# Main.net
KiCad netlist of a schematic drawn in EAGLE
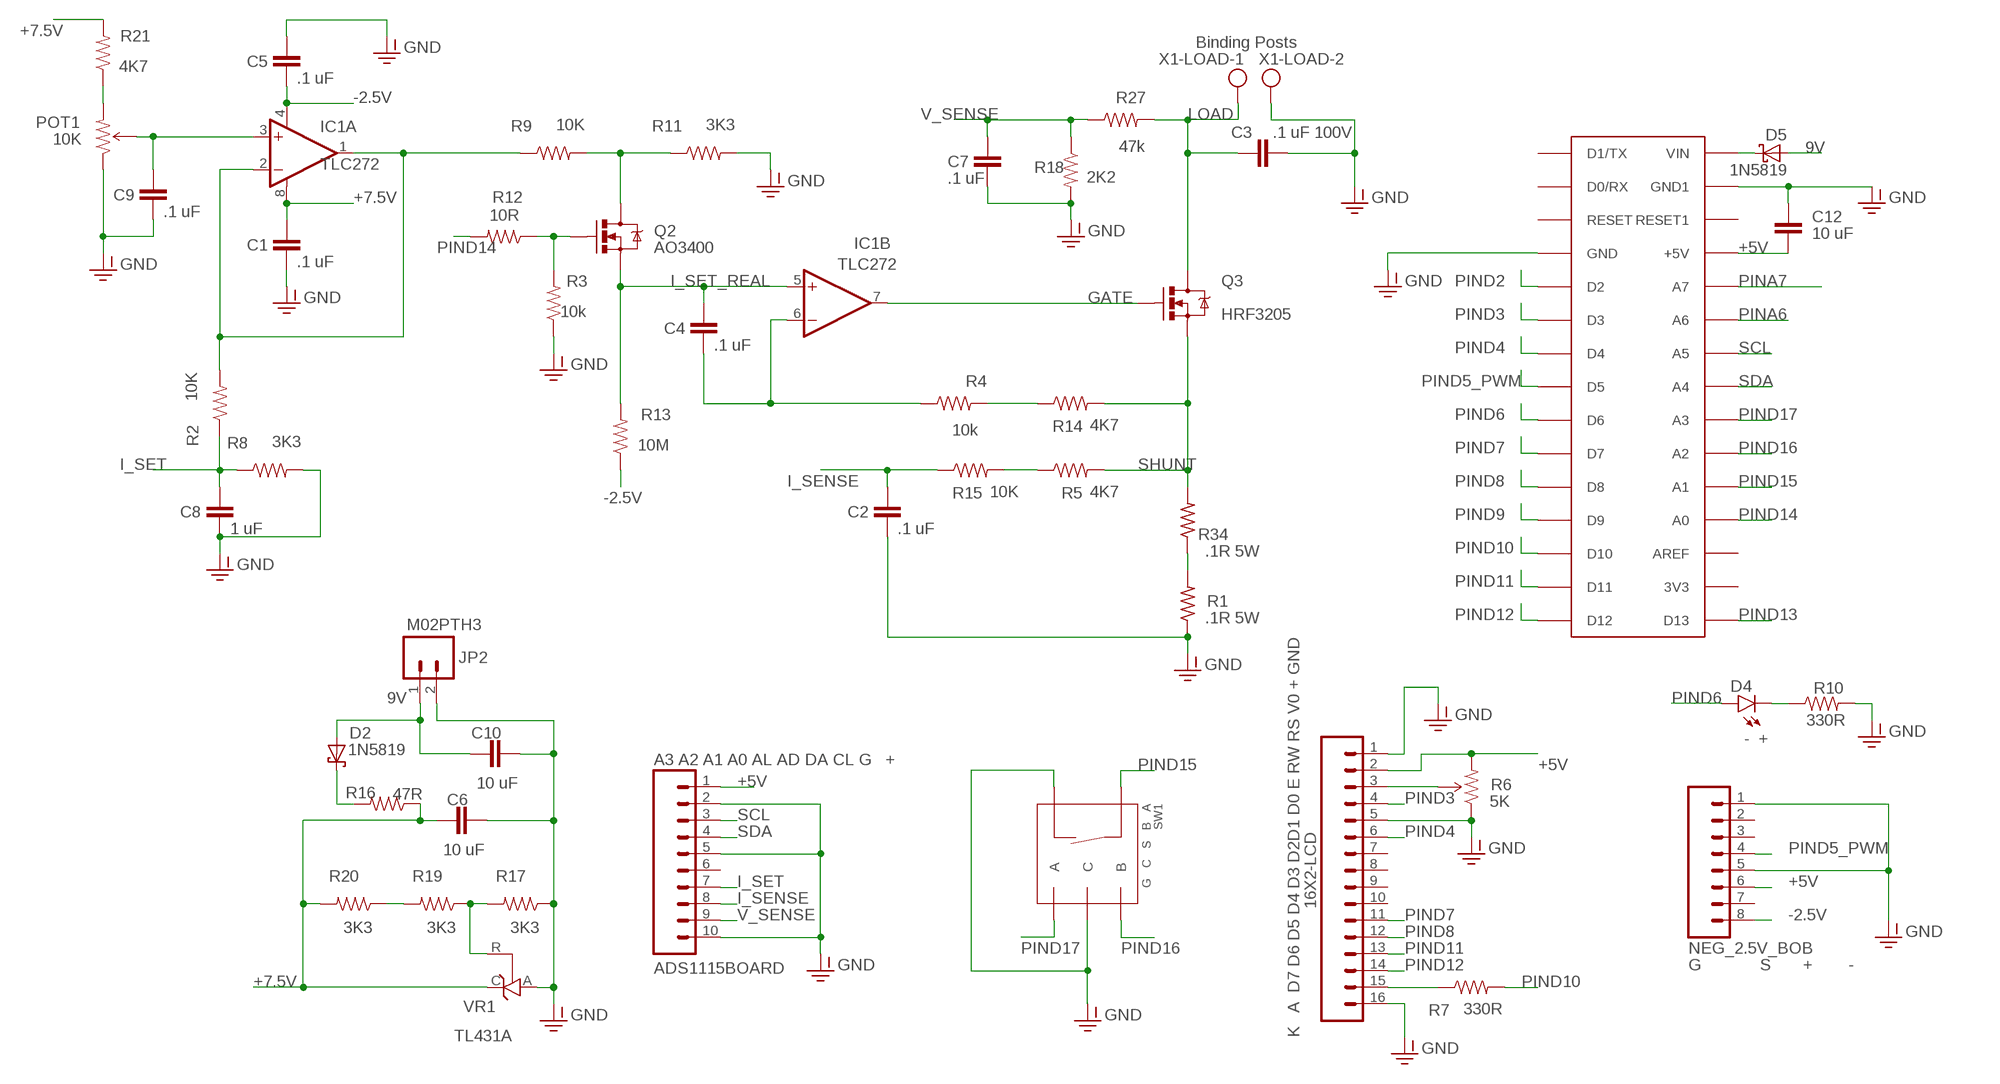
[diagram p0: schematic, sheet 1]
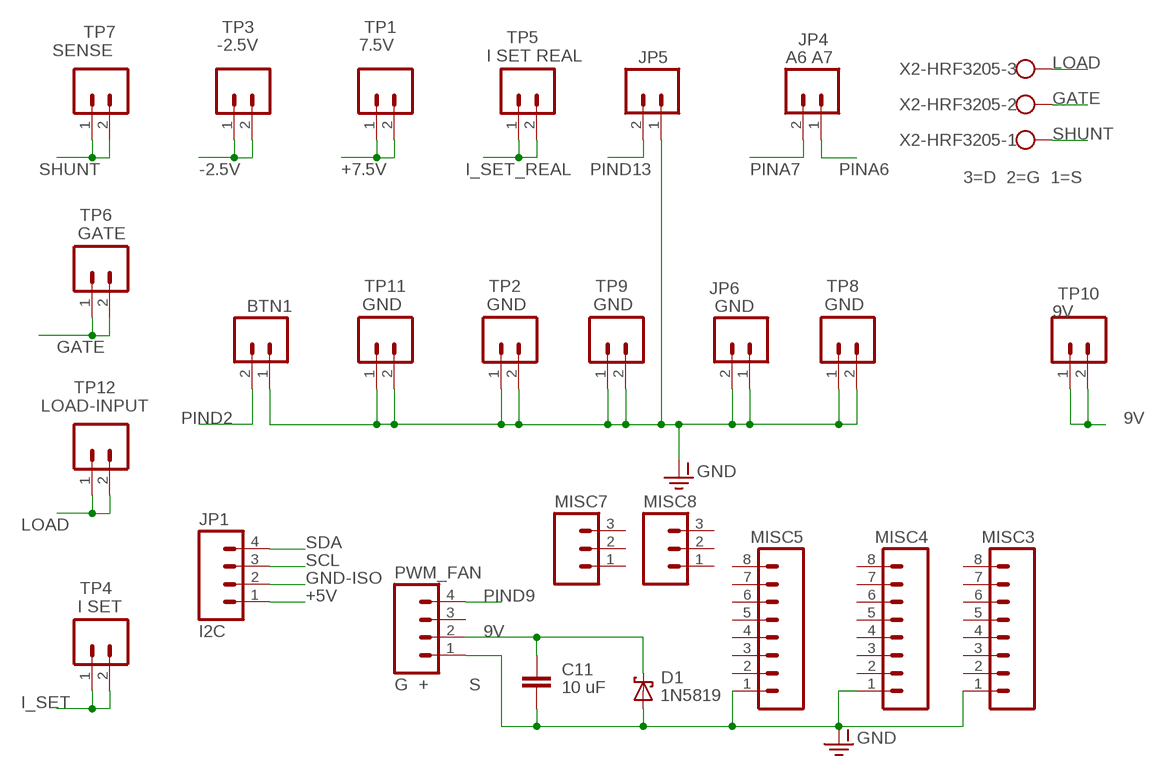
[diagram p1: schematic, sheet 2]

(export (version "E")
  (design (tool "Eeschema 10.0.6"))
  (components
    (comp (ref "BTN1")
      (value "M02PTH")
      (footprint "eagle-import:1X02")
      (libsource (lib "eagle-import") (part "M02PTH"))
    )
    (comp (ref "C11")
      (value "10 uF")
      (footprint "eagle-import:CAP-PTH-5MM")
      (libsource (lib "eagle-import") (part "CAPPTH1"))
    )
    (comp (ref "D1")
      (value "1N5819")
      (footprint "eagle-import:DO41-10")
      (libsource (lib "eagle-import") (part "1N5819"))
    )
    (comp (ref "JP1")
      (value "I2C")
      (footprint "eagle-import:1X04")
      (libsource (lib "eagle-import") (part "M04PTH"))
    )
    (comp (ref "JP4")
      (value "A6 A7")
      (footprint "eagle-import:1X02")
      (libsource (lib "eagle-import") (part "M02PTH"))
    )
    (comp (ref "JP5")
      (value "M02PTH")
      (footprint "eagle-import:1X02")
      (libsource (lib "eagle-import") (part "M02PTH"))
    )
    (comp (ref "JP6")
      (value "GND")
      (footprint "eagle-import:1X02")
      (libsource (lib "eagle-import") (part "M02PTH"))
    )
    (comp (ref "MISC3")
      (value "M08")
      (footprint "eagle-import:1X08_ROUND")
      (libsource (lib "eagle-import") (part "M08"))
    )
    (comp (ref "MISC4")
      (value "M08")
      (footprint "eagle-import:1X08_ROUND")
      (libsource (lib "eagle-import") (part "M08"))
    )
    (comp (ref "MISC5")
      (value "M08")
      (footprint "eagle-import:1X08_ROUND")
      (libsource (lib "eagle-import") (part "M08"))
    )
    (comp (ref "MISC7")
      (value "M03PTH")
      (footprint "eagle-import:1X03")
      (libsource (lib "eagle-import") (part "M03PTH"))
    )
    (comp (ref "MISC8")
      (value "M03PTH")
      (footprint "eagle-import:1X03")
      (libsource (lib "eagle-import") (part "M03PTH"))
    )
    (comp (ref "PWM_FAN")
      (value "G + S")
      (footprint "eagle-import:1X04")
      (libsource (lib "eagle-import") (part "M04PTH"))
    )
    (comp (ref "TP1")
      (value "7.5V")
      (footprint "eagle-import:1X02")
      (libsource (lib "eagle-import") (part "M02PTH"))
    )
    (comp (ref "TP2")
      (value "GND")
      (footprint "eagle-import:1X02_LONGPADS")
      (libsource (lib "eagle-import") (part "M02PTH3"))
    )
    (comp (ref "TP3")
      (value "-2.5V")
      (footprint "eagle-import:1X02")
      (libsource (lib "eagle-import") (part "M02PTH"))
    )
    (comp (ref "TP4")
      (value "I SET")
      (footprint "eagle-import:1X02_LONGPADS")
      (libsource (lib "eagle-import") (part "M02PTH3"))
    )
    (comp (ref "TP5")
      (value "I SET REAL")
      (footprint "eagle-import:1X02_LONGPADS")
      (libsource (lib "eagle-import") (part "M02PTH3"))
    )
    (comp (ref "TP6")
      (value "GATE")
      (footprint "eagle-import:1X02_LONGPADS")
      (libsource (lib "eagle-import") (part "M02PTH3"))
    )
    (comp (ref "TP7")
      (value "SENSE")
      (footprint "eagle-import:1X02_LONGPADS")
      (libsource (lib "eagle-import") (part "M02PTH3"))
    )
    (comp (ref "TP8")
      (value "GND")
      (footprint "eagle-import:1X02_LONGPADS")
      (libsource (lib "eagle-import") (part "M02PTH3"))
    )
    (comp (ref "TP9")
      (value "GND")
      (footprint "eagle-import:1X02_LONGPADS")
      (libsource (lib "eagle-import") (part "M02PTH3"))
    )
    (comp (ref "TP10")
      (value "9V")
      (footprint "eagle-import:1X02")
      (libsource (lib "eagle-import") (part "M02PTH"))
    )
    (comp (ref "TP11")
      (value "GND")
      (footprint "eagle-import:1X02_LONGPADS")
      (libsource (lib "eagle-import") (part "M02PTH3"))
    )
    (comp (ref "TP12")
      (value "LOAD-INPUT")
      (footprint "eagle-import:1X02_LONGPADS")
      (libsource (lib "eagle-import") (part "M02PTH3"))
    )
    (comp (ref "X2-HRF3205")
      (value "3=D 2=G 1=S")
      (footprint "eagle-import:W237-103")
      (fields (field (name "MPN") "237-103"))
      (libsource (lib "eagle-import") (part "W237-103"))
    )
    (comp (ref "16X2-LCD")
      (value "K A D7 D6 D5 D4 D3 D2D1 D0 E RW RS V0 + GND")
      (footprint "eagle-import:1X16")
      (libsource (lib "eagle-import") (part "M16PTH"))
    )
    (comp (ref "ADS1115BOARD")
      (value "A3 A2 A1 A0 AL AD DA CL G +")
      (footprint "eagle-import:1X10_NO_SILK")
      (libsource (lib "eagle-import") (part "M10NO_SILK_PTH_FEMALE"))
    )
    (comp (ref "ARDUINO_NANO")
      (value "NANO")
      (footprint "eagle-import:PDIP-32")
      (libsource (lib "eagle-import") (part "ARDUINONANO"))
    )
    (comp (ref "C1")
      (value ".1 uF")
      (footprint "eagle-import:CAP-PTH-5MM")
      (libsource (lib "eagle-import") (part "CAPPTH1"))
    )
    (comp (ref "C2")
      (value ".1 uF")
      (footprint "eagle-import:CAP-PTH-5MM")
      (libsource (lib "eagle-import") (part "CAPPTH1"))
    )
    (comp (ref "C3")
      (value ".1 uF 100V")
      (footprint "eagle-import:CAP-PTH-5MM")
      (libsource (lib "eagle-import") (part "CAPPTH1"))
    )
    (comp (ref "C4")
      (value ".1 uF")
      (footprint "eagle-import:CAP-PTH-5MM")
      (libsource (lib "eagle-import") (part "CAPPTH1"))
    )
    (comp (ref "C5")
      (value ".1 uF")
      (footprint "eagle-import:CAP-PTH-5MM")
      (libsource (lib "eagle-import") (part "CAPPTH1"))
    )
    (comp (ref "C6")
      (value "10 uF")
      (footprint "eagle-import:CAP-PTH-5MM")
      (libsource (lib "eagle-import") (part "CAPPTH1"))
    )
    (comp (ref "C7")
      (value ".1 uF")
      (footprint "eagle-import:CAP-PTH-5MM")
      (libsource (lib "eagle-import") (part "CAPPTH1"))
    )
    (comp (ref "C8")
      (value "1 uF")
      (footprint "eagle-import:CAP-PTH-5MM")
      (libsource (lib "eagle-import") (part "CAPPTH1"))
    )
    (comp (ref "C9")
      (value ".1 uF")
      (footprint "eagle-import:CAP-PTH-5MM")
      (libsource (lib "eagle-import") (part "CAPPTH1"))
    )
    (comp (ref "C10")
      (value "10 uF")
      (footprint "eagle-import:CAP-PTH-5MM")
      (libsource (lib "eagle-import") (part "CAPPTH1"))
    )
    (comp (ref "C12")
      (value "10 uF")
      (footprint "eagle-import:CAP-PTH-5MM")
      (libsource (lib "eagle-import") (part "CAPPTH1"))
    )
    (comp (ref "D2")
      (value "1N5819")
      (footprint "eagle-import:DO41-10")
      (libsource (lib "eagle-import") (part "1N5819"))
    )
    (comp (ref "D4")
      (value "- +")
      (footprint "eagle-import:LED5MM")
      (libsource (lib "eagle-import") (part "LED5MM"))
    )
    (comp (ref "D5")
      (value "1N5819")
      (footprint "eagle-import:DO41-10")
      (libsource (lib "eagle-import") (part "1N5819"))
    )
    (comp (ref "IC1")
      (value "TLC272")
      (footprint "eagle-import:DIP08")
      (libsource (lib "eagle-import") (part "OPAMP-DUALDIP"))
    )
    (comp (ref "JP2")
      (value "M02PTH3")
      (footprint "eagle-import:1X02_LONGPADS")
      (libsource (lib "eagle-import") (part "M02PTH3"))
    )
    (comp (ref "NEG_2.5V_BOB")
      (value "G S + -")
      (footprint "eagle-import:1X08_ROUND")
      (libsource (lib "eagle-import") (part "M08"))
    )
    (comp (ref "POT1")
      (value "10K")
      (footprint "eagle-import:3386U")
      (libsource (lib "eagle-import") (part "TRIMPOT-PTH-KNOB"))
    )
    (comp (ref "Q2")
      (value "AO3400")
      (footprint "eagle-import:SOT23-3")
      (libsource (lib "eagle-import") (part "MOSFET-NCHANNELBSS123LT1G"))
    )
    (comp (ref "Q3")
      (value "HRF3205")
      (footprint "eagle-import:TO220V")
      (libsource (lib "eagle-import") (part "MOSFET-NCHANNELFQP30N06L"))
    )
    (comp (ref "R1")
      (value ".1R 5W")
      (footprint "eagle-import:VTA53")
      (libsource (lib "eagle-import") (part "R-US_VTA53"))
    )
    (comp (ref "R2")
      (value "10K")
      (footprint "eagle-import:AXIAL-0.4")
      (libsource (lib "eagle-import") (part "RESISTORPTH-1/4W"))
    )
    (comp (ref "R3")
      (value "10k")
      (footprint "eagle-import:AXIAL-0.4")
      (libsource (lib "eagle-import") (part "RESISTORPTH-1/4W"))
    )
    (comp (ref "R4")
      (value "10k")
      (footprint "eagle-import:AXIAL-0.4")
      (libsource (lib "eagle-import") (part "RESISTORPTH-1/4W"))
    )
    (comp (ref "R5")
      (value "4K7")
      (footprint "eagle-import:AXIAL-0.4")
      (libsource (lib "eagle-import") (part "RESISTORPTH-1/4W"))
    )
    (comp (ref "R6")
      (value "5K")
      (footprint "eagle-import:TRIM_POT_PTH")
      (libsource (lib "eagle-import") (part "TRIMPOTPTH"))
    )
    (comp (ref "R7")
      (value "330R")
      (footprint "eagle-import:AXIAL-0.4")
      (libsource (lib "eagle-import") (part "RESISTORPTH-1/4W"))
    )
    (comp (ref "R8")
      (value "3K3")
      (footprint "eagle-import:AXIAL-0.5")
      (libsource (lib "eagle-import") (part "RESISTORPTH-1/2W"))
    )
    (comp (ref "R9")
      (value "10K")
      (footprint "eagle-import:AXIAL-0.4")
      (libsource (lib "eagle-import") (part "RESISTORPTH-1/4W"))
    )
    (comp (ref "R10")
      (value "330R")
      (footprint "eagle-import:AXIAL-0.4")
      (libsource (lib "eagle-import") (part "RESISTORPTH-1/4W"))
    )
    (comp (ref "R11")
      (value "3K3")
      (footprint "eagle-import:AXIAL-0.4")
      (libsource (lib "eagle-import") (part "RESISTORPTH-1/4W"))
    )
    (comp (ref "R12")
      (value "10R")
      (footprint "eagle-import:AXIAL-0.4")
      (libsource (lib "eagle-import") (part "RESISTORPTH-1/4W"))
    )
    (comp (ref "R13")
      (value "10M")
      (footprint "eagle-import:AXIAL-0.5")
      (libsource (lib "eagle-import") (part "RESISTORPTH-1/2W"))
    )
    (comp (ref "R14")
      (value "4K7")
      (footprint "eagle-import:AXIAL-0.4")
      (libsource (lib "eagle-import") (part "RESISTORPTH-1/4W"))
    )
    (comp (ref "R15")
      (value "10K")
      (footprint "eagle-import:AXIAL-0.5")
      (libsource (lib "eagle-import") (part "RESISTORPTH-1/2W"))
    )
    (comp (ref "R16")
      (value "47R")
      (footprint "eagle-import:AXIAL-0.4")
      (libsource (lib "eagle-import") (part "RESISTORPTH-1/4W"))
    )
    (comp (ref "R17")
      (value "3K3")
      (footprint "eagle-import:AXIAL-0.4")
      (libsource (lib "eagle-import") (part "RESISTORPTH-1/4W"))
    )
    (comp (ref "R18")
      (value "2K2")
      (footprint "eagle-import:AXIAL-0.4")
      (libsource (lib "eagle-import") (part "RESISTORPTH-1/4W"))
    )
    (comp (ref "R19")
      (value "3K3")
      (footprint "eagle-import:AXIAL-0.4")
      (libsource (lib "eagle-import") (part "RESISTORPTH-1/4W"))
    )
    (comp (ref "R20")
      (value "3K3")
      (footprint "eagle-import:AXIAL-0.4")
      (libsource (lib "eagle-import") (part "RESISTORPTH-1/4W"))
    )
    (comp (ref "R21")
      (value "4K7")
      (footprint "eagle-import:AXIAL-0.4")
      (libsource (lib "eagle-import") (part "RESISTORPTH-1/4W"))
    )
    (comp (ref "R27")
      (value "47k")
      (footprint "eagle-import:AXIAL-0.5")
      (libsource (lib "eagle-import") (part "RESISTORPTH-1/2W"))
    )
    (comp (ref "R34")
      (value ".1R 5W")
      (footprint "eagle-import:VTA53")
      (libsource (lib "eagle-import") (part "R-US_VTA53"))
    )
    (comp (ref "SW1")
      (value "G C S B A")
      (footprint "eagle-import:1X05")
      (libsource (lib "eagle-import") (part "ROTARTY_ENCODERROTARY_ENC_HDR"))
    )
    (comp (ref "VR1")
      (value "TL431A")
      (footprint "eagle-import:TO92-CLP")
      (libsource (lib "eagle-import") (part "TL431CLP"))
    )
    (comp (ref "X1-LOAD")
      (value "Binding Posts")
      (footprint "eagle-import:W237-102")
      (fields (field (name "MPN") "237-102"))
      (libsource (lib "eagle-import") (part "W237-102"))
    )
  )
  (nets
    (net (code "1") (name "+5V") (class "Default")
      (node (ref "16X2-LCD") (pin "2") (pinfunction "2_2") (pintype "passive"))
      (node (ref "ADS1115BOARD") (pin "1") (pinfunction "1_1") (pintype "passive"))
      (node (ref "ARDUINO_NANO") (pin "+5V") (pinfunction "+5V_+5V") (pintype "bidirectional"))
      (node (ref "C12") (pin "1") (pinfunction "1_1") (pintype "passive"))
      (node (ref "JP1") (pin "1") (pinfunction "1_1") (pintype "passive"))
      (node (ref "NEG_2.5V_BOB") (pin "6") (pinfunction "6_6") (pintype "passive"))
      (node (ref "R6") (pin "3") (pinfunction "CW_3") (pintype "passive"))
    )
    (net (code "2") (name "+7.5V") (class "Default")
      (node (ref "C1") (pin "1") (pinfunction "1_1") (pintype "passive"))
      (node (ref "C6") (pin "1") (pinfunction "1_1") (pintype "passive"))
      (node (ref "IC1") (pin "8") (pinfunction "V+_8") (pintype "power_in"))
      (node (ref "R16") (pin "P$1") (pinfunction "1_P$1") (pintype "passive"))
      (node (ref "R20") (pin "P$2") (pinfunction "2_P$2") (pintype "passive"))
      (node (ref "R21") (pin "P$2") (pinfunction "2_P$2") (pintype "passive"))
      (node (ref "TP1") (pin "1") (pinfunction "1_1") (pintype "passive"))
      (node (ref "TP1") (pin "2") (pinfunction "2_2") (pintype "passive"))
      (node (ref "VR1") (pin "C") (pinfunction "C_C") (pintype "passive"))
    )
    (net (code "3") (name "-2.5V") (class "Default")
      (node (ref "C5") (pin "2") (pinfunction "2_2") (pintype "passive"))
      (node (ref "IC1") (pin "4") (pinfunction "V-_4") (pintype "power_in"))
      (node (ref "NEG_2.5V_BOB") (pin "8") (pinfunction "8_8") (pintype "passive"))
      (node (ref "R13") (pin "P$1") (pinfunction "1_P$1") (pintype "passive"))
      (node (ref "TP3") (pin "1") (pinfunction "1_1") (pintype "passive"))
      (node (ref "TP3") (pin "2") (pinfunction "2_2") (pintype "passive"))
    )
    (net (code "4") (name "9V") (class "Default")
      (node (ref "C10") (pin "1") (pinfunction "1_1") (pintype "passive"))
      (node (ref "C11") (pin "2") (pinfunction "2_2") (pintype "passive"))
      (node (ref "D1") (pin "C") (pinfunction "C_C") (pintype "passive"))
      (node (ref "D2") (pin "A") (pinfunction "A_A") (pintype "passive"))
      (node (ref "D5") (pin "A") (pinfunction "A_A") (pintype "passive"))
      (node (ref "JP2") (pin "1") (pinfunction "1_1") (pintype "passive"))
      (node (ref "PWM_FAN") (pin "2") (pinfunction "2_2") (pintype "passive"))
      (node (ref "TP10") (pin "1") (pinfunction "1_1") (pintype "passive"))
      (node (ref "TP10") (pin "2") (pinfunction "2_2") (pintype "passive"))
    )
    (net (code "5") (name "GATE") (class "Default")
      (node (ref "IC1") (pin "7") (pinfunction "OUT_7") (pintype "output"))
      (node (ref "Q3") (pin "1") (pinfunction "G_1") (pintype "passive"))
      (node (ref "TP6") (pin "1") (pinfunction "1_1") (pintype "passive"))
      (node (ref "TP6") (pin "2") (pinfunction "2_2") (pintype "passive"))
      (node (ref "X2-HRF3205") (pin "2") (pinfunction "KL_2") (pintype "passive"))
    )
    (net (code "6") (name "GND-ISO") (class "Default")
      (node (ref "16X2-LCD") (pin "1") (pinfunction "1_1") (pintype "passive"))
      (node (ref "16X2-LCD") (pin "16") (pinfunction "16_16") (pintype "passive"))
      (node (ref "16X2-LCD") (pin "5") (pinfunction "5_5") (pintype "passive"))
      (node (ref "ADS1115BOARD") (pin "10") (pinfunction "10_10") (pintype "passive"))
      (node (ref "ADS1115BOARD") (pin "2") (pinfunction "2_2") (pintype "passive"))
      (node (ref "ADS1115BOARD") (pin "5") (pinfunction "5_5") (pintype "passive"))
      (node (ref "ARDUINO_NANO") (pin "GND") (pinfunction "GND_GND") (pintype "bidirectional"))
      (node (ref "ARDUINO_NANO") (pin "GND1") (pinfunction "GND1_GND1") (pintype "bidirectional"))
      (node (ref "BTN1") (pin "1") (pinfunction "1_1") (pintype "passive"))
      (node (ref "C1") (pin "2") (pinfunction "2_2") (pintype "passive"))
      (node (ref "C10") (pin "2") (pinfunction "2_2") (pintype "passive"))
      (node (ref "C11") (pin "1") (pinfunction "1_1") (pintype "passive"))
      (node (ref "C12") (pin "2") (pinfunction "2_2") (pintype "passive"))
      (node (ref "C2") (pin "2") (pinfunction "2_2") (pintype "passive"))
      (node (ref "C3") (pin "2") (pinfunction "2_2") (pintype "passive"))
      (node (ref "C5") (pin "1") (pinfunction "1_1") (pintype "passive"))
      (node (ref "C6") (pin "2") (pinfunction "2_2") (pintype "passive"))
      (node (ref "C7") (pin "2") (pinfunction "2_2") (pintype "passive"))
      (node (ref "C8") (pin "2") (pinfunction "2_2") (pintype "passive"))
      (node (ref "C9") (pin "2") (pinfunction "2_2") (pintype "passive"))
      (node (ref "D1") (pin "A") (pinfunction "A_A") (pintype "passive"))
      (node (ref "JP1") (pin "2") (pinfunction "2_2") (pintype "passive"))
      (node (ref "JP2") (pin "2") (pinfunction "2_2") (pintype "passive"))
      (node (ref "JP5") (pin "1") (pinfunction "1_1") (pintype "passive"))
      (node (ref "JP6") (pin "1") (pinfunction "1_1") (pintype "passive"))
      (node (ref "JP6") (pin "2") (pinfunction "2_2") (pintype "passive"))
      (node (ref "MISC3") (pin "1") (pinfunction "1_1") (pintype "passive"))
      (node (ref "MISC4") (pin "1") (pinfunction "1_1") (pintype "passive"))
      (node (ref "MISC5") (pin "1") (pinfunction "1_1") (pintype "passive"))
      (node (ref "NEG_2.5V_BOB") (pin "1") (pinfunction "1_1") (pintype "passive"))
      (node (ref "NEG_2.5V_BOB") (pin "5") (pinfunction "5_5") (pintype "passive"))
      (node (ref "POT1") (pin "1") (pinfunction "CCW_1") (pintype "passive"))
      (node (ref "PWM_FAN") (pin "1") (pinfunction "1_1") (pintype "passive"))
      (node (ref "R1") (pin "1") (pinfunction "1_1") (pintype "passive"))
      (node (ref "R10") (pin "P$2") (pinfunction "2_P$2") (pintype "passive"))
      (node (ref "R11") (pin "P$2") (pinfunction "2_P$2") (pintype "passive"))
      (node (ref "R17") (pin "P$1") (pinfunction "1_P$1") (pintype "passive"))
      (node (ref "R18") (pin "P$2") (pinfunction "2_P$2") (pintype "passive"))
      (node (ref "R3") (pin "P$1") (pinfunction "1_P$1") (pintype "passive"))
      (node (ref "R6") (pin "1") (pinfunction "CCW_1") (pintype "passive"))
      (node (ref "R8") (pin "P$2") (pinfunction "2_P$2") (pintype "passive"))
      (node (ref "SW1") (pin "1") (pinfunction "SW-_1") (pintype "bidirectional"))
      (node (ref "SW1") (pin "2") (pinfunction "C_2") (pintype "bidirectional"))
      (node (ref "TP11") (pin "1") (pinfunction "1_1") (pintype "passive"))
      (node (ref "TP11") (pin "2") (pinfunction "2_2") (pintype "passive"))
      (node (ref "TP2") (pin "1") (pinfunction "1_1") (pintype "passive"))
      (node (ref "TP2") (pin "2") (pinfunction "2_2") (pintype "passive"))
      (node (ref "TP8") (pin "1") (pinfunction "1_1") (pintype "passive"))
      (node (ref "TP8") (pin "2") (pinfunction "2_2") (pintype "passive"))
      (node (ref "TP9") (pin "1") (pinfunction "1_1") (pintype "passive"))
      (node (ref "TP9") (pin "2") (pinfunction "2_2") (pintype "passive"))
      (node (ref "VR1") (pin "A") (pinfunction "A_A") (pintype "passive"))
      (node (ref "X1-LOAD") (pin "2") (pinfunction "KL_2") (pintype "passive"))
    )
    (net (code "7") (name "I_SENSE") (class "Default")
      (node (ref "ADS1115BOARD") (pin "8") (pinfunction "8_8") (pintype "passive"))
      (node (ref "C2") (pin "1") (pinfunction "1_1") (pintype "passive"))
      (node (ref "R15") (pin "P$1") (pinfunction "1_P$1") (pintype "passive"))
    )
    (net (code "8") (name "I_SET") (class "Default")
      (node (ref "ADS1115BOARD") (pin "7") (pinfunction "7_7") (pintype "passive"))
      (node (ref "C8") (pin "1") (pinfunction "1_1") (pintype "passive"))
      (node (ref "R2") (pin "P$1") (pinfunction "1_P$1") (pintype "passive"))
      (node (ref "R8") (pin "P$1") (pinfunction "1_P$1") (pintype "passive"))
      (node (ref "TP4") (pin "1") (pinfunction "1_1") (pintype "passive"))
      (node (ref "TP4") (pin "2") (pinfunction "2_2") (pintype "passive"))
    )
    (net (code "9") (name "I_SET_REAL") (class "Default")
      (node (ref "C4") (pin "1") (pinfunction "1_1") (pintype "passive"))
      (node (ref "IC1") (pin "5") (pinfunction "+IN_5") (pintype "input"))
      (node (ref "Q2") (pin "2") (pinfunction "S_2") (pintype "passive"))
      (node (ref "R13") (pin "P$2") (pinfunction "2_P$2") (pintype "passive"))
      (node (ref "TP5") (pin "1") (pinfunction "1_1") (pintype "passive"))
      (node (ref "TP5") (pin "2") (pinfunction "2_2") (pintype "passive"))
    )
    (net (code "10") (name "LOAD") (class "Default")
      (node (ref "C3") (pin "1") (pinfunction "1_1") (pintype "passive"))
      (node (ref "Q3") (pin "2") (pinfunction "D_2") (pintype "passive"))
      (node (ref "R27") (pin "P$2") (pinfunction "2_P$2") (pintype "passive"))
      (node (ref "TP12") (pin "1") (pinfunction "1_1") (pintype "passive"))
      (node (ref "TP12") (pin "2") (pinfunction "2_2") (pintype "passive"))
      (node (ref "X1-LOAD") (pin "1") (pinfunction "KL_1") (pintype "passive"))
      (node (ref "X2-HRF3205") (pin "3") (pinfunction "KL_3") (pintype "passive"))
    )
    (net (code "11") (name "Net-(ARDUINO_NANO-PadVIN)") (class "Default")
      (node (ref "ARDUINO_NANO") (pin "VIN") (pinfunction "VIN_VIN") (pintype "bidirectional"))
      (node (ref "D5") (pin "C") (pinfunction "C_C") (pintype "passive"))
    )
    (net (code "12") (name "Net-(D4-C)") (class "Default")
      (node (ref "D4") (pin "K") (pinfunction "C_K") (pintype "passive"))
      (node (ref "R10") (pin "P$1") (pinfunction "1_P$1") (pintype "passive"))
    )
    (net (code "13") (name "Net-(IC1A-+IN)") (class "Default")
      (node (ref "C9") (pin "1") (pinfunction "1_1") (pintype "passive"))
      (node (ref "IC1") (pin "3") (pinfunction "+IN_3") (pintype "input"))
      (node (ref "POT1") (pin "2") (pinfunction "WIPER_2") (pintype "passive"))
    )
    (net (code "14") (name "Net-(IC1A--IN)") (class "Default")
      (node (ref "IC1") (pin "1") (pinfunction "OUT_1") (pintype "output"))
      (node (ref "IC1") (pin "2") (pinfunction "-IN_2") (pintype "input"))
      (node (ref "R2") (pin "P$2") (pinfunction "2_P$2") (pintype "passive"))
      (node (ref "R9") (pin "P$1") (pinfunction "1_P$1") (pintype "passive"))
    )
    (net (code "15") (name "Net-(IC1B--IN)") (class "Default")
      (node (ref "C4") (pin "2") (pinfunction "2_2") (pintype "passive"))
      (node (ref "IC1") (pin "6") (pinfunction "-IN_6") (pintype "input"))
      (node (ref "R4") (pin "P$1") (pinfunction "1_P$1") (pintype "passive"))
    )
    (net (code "16") (name "Net-(POT1-CW)") (class "Default")
      (node (ref "POT1") (pin "3") (pinfunction "CW_3") (pintype "passive"))
      (node (ref "R21") (pin "P$1") (pinfunction "1_P$1") (pintype "passive"))
    )
    (net (code "17") (name "Net-(Q2-D)") (class "Default")
      (node (ref "Q2") (pin "3") (pinfunction "D_3") (pintype "passive"))
      (node (ref "R11") (pin "P$1") (pinfunction "1_P$1") (pintype "passive"))
      (node (ref "R9") (pin "P$2") (pinfunction "2_P$2") (pintype "passive"))
    )
    (net (code "18") (name "Net-(Q2-G)") (class "Default")
      (node (ref "Q2") (pin "1") (pinfunction "G_1") (pintype "passive"))
      (node (ref "R12") (pin "P$1") (pinfunction "1_P$1") (pintype "passive"))
      (node (ref "R3") (pin "P$2") (pinfunction "2_P$2") (pintype "passive"))
    )
    (net (code "19") (name "Net-(R1-Pad2)") (class "Default")
      (node (ref "R1") (pin "2") (pinfunction "2_2") (pintype "passive"))
      (node (ref "R34") (pin "1") (pinfunction "1_1") (pintype "passive"))
    )
    (net (code "20") (name "Net-(R6-WIPER)") (class "Default")
      (node (ref "16X2-LCD") (pin "3") (pinfunction "3_3") (pintype "passive"))
      (node (ref "R6") (pin "2") (pinfunction "WIPER_2") (pintype "passive"))
    )
    (net (code "21") (name "Net-(R7-1)") (class "Default")
      (node (ref "16X2-LCD") (pin "15") (pinfunction "15_15") (pintype "passive"))
      (node (ref "R7") (pin "P$1") (pinfunction "1_P$1") (pintype "passive"))
    )
    (net (code "22") (name "Net-(R14-1)") (class "Default")
      (node (ref "R14") (pin "P$1") (pinfunction "1_P$1") (pintype "passive"))
      (node (ref "R4") (pin "P$2") (pinfunction "2_P$2") (pintype "passive"))
    )
    (net (code "23") (name "Net-(R15-2)") (class "Default")
      (node (ref "R15") (pin "P$2") (pinfunction "2_P$2") (pintype "passive"))
      (node (ref "R5") (pin "P$1") (pinfunction "1_P$1") (pintype "passive"))
    )
    (net (code "24") (name "Net-(R16-2)") (class "Default")
      (node (ref "D2") (pin "C") (pinfunction "C_C") (pintype "passive"))
      (node (ref "R16") (pin "P$2") (pinfunction "2_P$2") (pintype "passive"))
    )
    (net (code "25") (name "Net-(R17-2)") (class "Default")
      (node (ref "R17") (pin "P$2") (pinfunction "2_P$2") (pintype "passive"))
      (node (ref "R19") (pin "P$1") (pinfunction "1_P$1") (pintype "passive"))
      (node (ref "VR1") (pin "R") (pinfunction "R_R") (pintype "passive"))
    )
    (net (code "26") (name "Net-(R19-2)") (class "Default")
      (node (ref "R19") (pin "P$2") (pinfunction "2_P$2") (pintype "passive"))
      (node (ref "R20") (pin "P$1") (pinfunction "1_P$1") (pintype "passive"))
    )
    (net (code "27") (name "PINA6") (class "Default")
      (node (ref "ARDUINO_NANO") (pin "A1") (pinfunction "A6_A1") (pintype "bidirectional"))
      (node (ref "JP4") (pin "1") (pinfunction "1_1") (pintype "passive"))
    )
    (net (code "28") (name "PINA7") (class "Default")
      (node (ref "ARDUINO_NANO") (pin "A0") (pinfunction "A7_A0") (pintype "bidirectional"))
      (node (ref "JP4") (pin "2") (pinfunction "2_2") (pintype "passive"))
    )
    (net (code "29") (name "PIND2") (class "Default")
      (node (ref "ARDUINO_NANO") (pin "D2") (pinfunction "D2_D2") (pintype "bidirectional"))
      (node (ref "BTN1") (pin "2") (pinfunction "2_2") (pintype "passive"))
    )
    (net (code "30") (name "PIND3") (class "Default")
      (node (ref "16X2-LCD") (pin "4") (pinfunction "4_4") (pintype "passive"))
      (node (ref "ARDUINO_NANO") (pin "D3") (pinfunction "D3_D3") (pintype "bidirectional"))
    )
    (net (code "31") (name "PIND4") (class "Default")
      (node (ref "16X2-LCD") (pin "6") (pinfunction "6_6") (pintype "passive"))
      (node (ref "ARDUINO_NANO") (pin "D4") (pinfunction "D4_D4") (pintype "bidirectional"))
    )
    (net (code "32") (name "PIND5_PWM") (class "Default")
      (node (ref "ARDUINO_NANO") (pin "D5") (pinfunction "D5_D5") (pintype "bidirectional"))
      (node (ref "NEG_2.5V_BOB") (pin "4") (pinfunction "4_4") (pintype "passive"))
    )
    (net (code "33") (name "PIND6") (class "Default")
      (node (ref "ARDUINO_NANO") (pin "D6") (pinfunction "D6_D6") (pintype "bidirectional"))
      (node (ref "D4") (pin "A") (pinfunction "A_A") (pintype "passive"))
    )
    (net (code "34") (name "PIND7") (class "Default")
      (node (ref "16X2-LCD") (pin "11") (pinfunction "11_11") (pintype "passive"))
      (node (ref "ARDUINO_NANO") (pin "D7") (pinfunction "D7_D7") (pintype "bidirectional"))
    )
    (net (code "35") (name "PIND8") (class "Default")
      (node (ref "16X2-LCD") (pin "12") (pinfunction "12_12") (pintype "passive"))
      (node (ref "ARDUINO_NANO") (pin "D8") (pinfunction "D8_D8") (pintype "bidirectional"))
    )
    (net (code "36") (name "PIND9") (class "Default")
      (node (ref "ARDUINO_NANO") (pin "D9") (pinfunction "D9_D9") (pintype "bidirectional"))
      (node (ref "PWM_FAN") (pin "4") (pinfunction "4_4") (pintype "passive"))
    )
    (net (code "37") (name "PIND10") (class "Default")
      (node (ref "ARDUINO_NANO") (pin "D10") (pinfunction "D10_D10") (pintype "bidirectional"))
      (node (ref "R7") (pin "P$2") (pinfunction "2_P$2") (pintype "passive"))
    )
    (net (code "38") (name "PIND11") (class "Default")
      (node (ref "16X2-LCD") (pin "13") (pinfunction "13_13") (pintype "passive"))
      (node (ref "ARDUINO_NANO") (pin "D11") (pinfunction "D11_D11") (pintype "bidirectional"))
    )
    (net (code "39") (name "PIND12") (class "Default")
      (node (ref "16X2-LCD") (pin "14") (pinfunction "14_14") (pintype "passive"))
      (node (ref "ARDUINO_NANO") (pin "D12") (pinfunction "D12_D12") (pintype "bidirectional"))
    )
    (net (code "40") (name "PIND13") (class "Default")
      (node (ref "ARDUINO_NANO") (pin "D13") (pinfunction "D13_D13") (pintype "bidirectional"))
      (node (ref "JP5") (pin "2") (pinfunction "2_2") (pintype "passive"))
    )
    (net (code "41") (name "PIND14") (class "Default")
      (node (ref "ARDUINO_NANO") (pin "A7") (pinfunction "A0_A7") (pintype "bidirectional"))
      (node (ref "R12") (pin "P$2") (pinfunction "2_P$2") (pintype "passive"))
    )
    (net (code "42") (name "PIND15") (class "Default")
      (node (ref "ARDUINO_NANO") (pin "A6") (pinfunction "A1_A6") (pintype "bidirectional"))
      (node (ref "SW1") (pin "3") (pinfunction "SW+_3") (pintype "bidirectional"))
    )
    (net (code "43") (name "PIND16") (class "Default")
      (node (ref "ARDUINO_NANO") (pin "A5") (pinfunction "A2_A5") (pintype "bidirectional"))
      (node (ref "SW1") (pin "4") (pinfunction "B_4") (pintype "bidirectional"))
    )
    (net (code "44") (name "PIND17") (class "Default")
      (node (ref "ARDUINO_NANO") (pin "A4") (pinfunction "A3_A4") (pintype "bidirectional"))
      (node (ref "SW1") (pin "5") (pinfunction "A_5") (pintype "bidirectional"))
    )
    (net (code "45") (name "SCL") (class "Default")
      (node (ref "ADS1115BOARD") (pin "3") (pinfunction "3_3") (pintype "passive"))
      (node (ref "ARDUINO_NANO") (pin "A2") (pinfunction "A5_A2") (pintype "bidirectional"))
      (node (ref "JP1") (pin "3") (pinfunction "3_3") (pintype "passive"))
    )
    (net (code "46") (name "SDA") (class "Default")
      (node (ref "ADS1115BOARD") (pin "4") (pinfunction "4_4") (pintype "passive"))
      (node (ref "ARDUINO_NANO") (pin "A3") (pinfunction "A4_A3") (pintype "bidirectional"))
      (node (ref "JP1") (pin "4") (pinfunction "4_4") (pintype "passive"))
    )
    (net (code "47") (name "SHUNT") (class "Default")
      (node (ref "Q3") (pin "3") (pinfunction "S_3") (pintype "passive"))
      (node (ref "R14") (pin "P$2") (pinfunction "2_P$2") (pintype "passive"))
      (node (ref "R34") (pin "2") (pinfunction "2_2") (pintype "passive"))
      (node (ref "R5") (pin "P$2") (pinfunction "2_P$2") (pintype "passive"))
      (node (ref "TP7") (pin "1") (pinfunction "1_1") (pintype "passive"))
      (node (ref "TP7") (pin "2") (pinfunction "2_2") (pintype "passive"))
      (node (ref "X2-HRF3205") (pin "1") (pinfunction "KL_1") (pintype "passive"))
    )
    (net (code "48") (name "V_SENSE") (class "Default")
      (node (ref "ADS1115BOARD") (pin "9") (pinfunction "9_9") (pintype "passive"))
      (node (ref "C7") (pin "1") (pinfunction "1_1") (pintype "passive"))
      (node (ref "R18") (pin "P$1") (pinfunction "1_P$1") (pintype "passive"))
      (node (ref "R27") (pin "P$1") (pinfunction "1_P$1") (pintype "passive"))
    )
    (net (code "49") (name "unconnected-(16X2-LCD-Pad7)") (class "Default")
      (node (ref "16X2-LCD") (pin "7") (pinfunction "7_7") (pintype "passive"))
    )
    (net (code "50") (name "unconnected-(16X2-LCD-Pad8)") (class "Default")
      (node (ref "16X2-LCD") (pin "8") (pinfunction "8_8") (pintype "passive"))
    )
    (net (code "51") (name "unconnected-(16X2-LCD-Pad9)") (class "Default")
      (node (ref "16X2-LCD") (pin "9") (pinfunction "9_9") (pintype "passive"))
    )
    (net (code "52") (name "unconnected-(16X2-LCD-Pad10)") (class "Default")
      (node (ref "16X2-LCD") (pin "10") (pinfunction "10_10") (pintype "passive"))
    )
    (net (code "53") (name "unconnected-(ADS1115BOARD-Pad6)") (class "Default")
      (node (ref "ADS1115BOARD") (pin "6") (pinfunction "6_6") (pintype "passive"))
    )
    (net (code "54") (name "unconnected-(ARDUINO_NANO-Pad3V3)") (class "Default")
      (node (ref "ARDUINO_NANO") (pin "3V3") (pinfunction "3V3_3V3") (pintype "bidirectional"))
    )
    (net (code "55") (name "unconnected-(ARDUINO_NANO-PadAREF)") (class "Default")
      (node (ref "ARDUINO_NANO") (pin "AREF") (pinfunction "AREF_AREF") (pintype "bidirectional"))
    )
    (net (code "56") (name "unconnected-(ARDUINO_NANO-PadD0{slash}RX)") (class "Default")
      (node (ref "ARDUINO_NANO") (pin "D0/RX") (pinfunction "D0/RX_D0/RX") (pintype "bidirectional"))
    )
    (net (code "57") (name "unconnected-(ARDUINO_NANO-PadD1{slash}TX)") (class "Default")
      (node (ref "ARDUINO_NANO") (pin "D1/TX") (pinfunction "D1/TX_D1/TX") (pintype "bidirectional"))
    )
    (net (code "58") (name "unconnected-(ARDUINO_NANO-PadRESET)") (class "Default")
      (node (ref "ARDUINO_NANO") (pin "RESET") (pinfunction "RESET_RESET") (pintype "bidirectional"))
    )
    (net (code "59") (name "unconnected-(ARDUINO_NANO-PadRESET1)") (class "Default")
      (node (ref "ARDUINO_NANO") (pin "RESET1") (pinfunction "RESET1_RESET1") (pintype "bidirectional"))
    )
    (net (code "60") (name "unconnected-(MISC3-Pad2)") (class "Default")
      (node (ref "MISC3") (pin "2") (pinfunction "2_2") (pintype "passive"))
    )
    (net (code "61") (name "unconnected-(MISC3-Pad3)") (class "Default")
      (node (ref "MISC3") (pin "3") (pinfunction "3_3") (pintype "passive"))
    )
    (net (code "62") (name "unconnected-(MISC3-Pad4)") (class "Default")
      (node (ref "MISC3") (pin "4") (pinfunction "4_4") (pintype "passive"))
    )
    (net (code "63") (name "unconnected-(MISC3-Pad5)") (class "Default")
      (node (ref "MISC3") (pin "5") (pinfunction "5_5") (pintype "passive"))
    )
    (net (code "64") (name "unconnected-(MISC3-Pad6)") (class "Default")
      (node (ref "MISC3") (pin "6") (pinfunction "6_6") (pintype "passive"))
    )
    (net (code "65") (name "unconnected-(MISC3-Pad7)") (class "Default")
      (node (ref "MISC3") (pin "7") (pinfunction "7_7") (pintype "passive"))
    )
    (net (code "66") (name "unconnected-(MISC3-Pad8)") (class "Default")
      (node (ref "MISC3") (pin "8") (pinfunction "8_8") (pintype "passive"))
    )
    (net (code "67") (name "unconnected-(MISC4-Pad2)") (class "Default")
      (node (ref "MISC4") (pin "2") (pinfunction "2_2") (pintype "passive"))
    )
    (net (code "68") (name "unconnected-(MISC4-Pad3)") (class "Default")
      (node (ref "MISC4") (pin "3") (pinfunction "3_3") (pintype "passive"))
    )
    (net (code "69") (name "unconnected-(MISC4-Pad4)") (class "Default")
      (node (ref "MISC4") (pin "4") (pinfunction "4_4") (pintype "passive"))
    )
    (net (code "70") (name "unconnected-(MISC4-Pad5)") (class "Default")
      (node (ref "MISC4") (pin "5") (pinfunction "5_5") (pintype "passive"))
    )
    (net (code "71") (name "unconnected-(MISC4-Pad6)") (class "Default")
      (node (ref "MISC4") (pin "6") (pinfunction "6_6") (pintype "passive"))
    )
    (net (code "72") (name "unconnected-(MISC4-Pad7)") (class "Default")
      (node (ref "MISC4") (pin "7") (pinfunction "7_7") (pintype "passive"))
    )
    (net (code "73") (name "unconnected-(MISC4-Pad8)") (class "Default")
      (node (ref "MISC4") (pin "8") (pinfunction "8_8") (pintype "passive"))
    )
    (net (code "74") (name "unconnected-(MISC5-Pad2)") (class "Default")
      (node (ref "MISC5") (pin "2") (pinfunction "2_2") (pintype "passive"))
    )
    (net (code "75") (name "unconnected-(MISC5-Pad3)") (class "Default")
      (node (ref "MISC5") (pin "3") (pinfunction "3_3") (pintype "passive"))
    )
    (net (code "76") (name "unconnected-(MISC5-Pad4)") (class "Default")
      (node (ref "MISC5") (pin "4") (pinfunction "4_4") (pintype "passive"))
    )
    (net (code "77") (name "unconnected-(MISC5-Pad5)") (class "Default")
      (node (ref "MISC5") (pin "5") (pinfunction "5_5") (pintype "passive"))
    )
    (net (code "78") (name "unconnected-(MISC5-Pad6)") (class "Default")
      (node (ref "MISC5") (pin "6") (pinfunction "6_6") (pintype "passive"))
    )
    (net (code "79") (name "unconnected-(MISC5-Pad7)") (class "Default")
      (node (ref "MISC5") (pin "7") (pinfunction "7_7") (pintype "passive"))
    )
    (net (code "80") (name "unconnected-(MISC5-Pad8)") (class "Default")
      (node (ref "MISC5") (pin "8") (pinfunction "8_8") (pintype "passive"))
    )
    (net (code "81") (name "unconnected-(MISC7-Pad1)") (class "Default")
      (node (ref "MISC7") (pin "1") (pinfunction "1_1") (pintype "passive"))
    )
    (net (code "82") (name "unconnected-(MISC7-Pad2)") (class "Default")
      (node (ref "MISC7") (pin "2") (pinfunction "2_2") (pintype "passive"))
    )
    (net (code "83") (name "unconnected-(MISC7-Pad3)") (class "Default")
      (node (ref "MISC7") (pin "3") (pinfunction "3_3") (pintype "passive"))
    )
    (net (code "84") (name "unconnected-(MISC8-Pad1)") (class "Default")
      (node (ref "MISC8") (pin "1") (pinfunction "1_1") (pintype "passive"))
    )
    (net (code "85") (name "unconnected-(MISC8-Pad2)") (class "Default")
      (node (ref "MISC8") (pin "2") (pinfunction "2_2") (pintype "passive"))
    )
    (net (code "86") (name "unconnected-(MISC8-Pad3)") (class "Default")
      (node (ref "MISC8") (pin "3") (pinfunction "3_3") (pintype "passive"))
    )
    (net (code "87") (name "unconnected-(NEG_2.5V_BOB-Pad2)") (class "Default")
      (node (ref "NEG_2.5V_BOB") (pin "2") (pinfunction "2_2") (pintype "passive"))
    )
    (net (code "88") (name "unconnected-(NEG_2.5V_BOB-Pad3)") (class "Default")
      (node (ref "NEG_2.5V_BOB") (pin "3") (pinfunction "3_3") (pintype "passive"))
    )
    (net (code "89") (name "unconnected-(NEG_2.5V_BOB-Pad7)") (class "Default")
      (node (ref "NEG_2.5V_BOB") (pin "7") (pinfunction "7_7") (pintype "passive"))
    )
    (net (code "90") (name "unconnected-(PWM_FAN-Pad3)") (class "Default")
      (node (ref "PWM_FAN") (pin "3") (pinfunction "3_3") (pintype "passive"))
    )
  )
)
